# MCU.net
KiCad netlist of a schematic drawn in Altium Designer
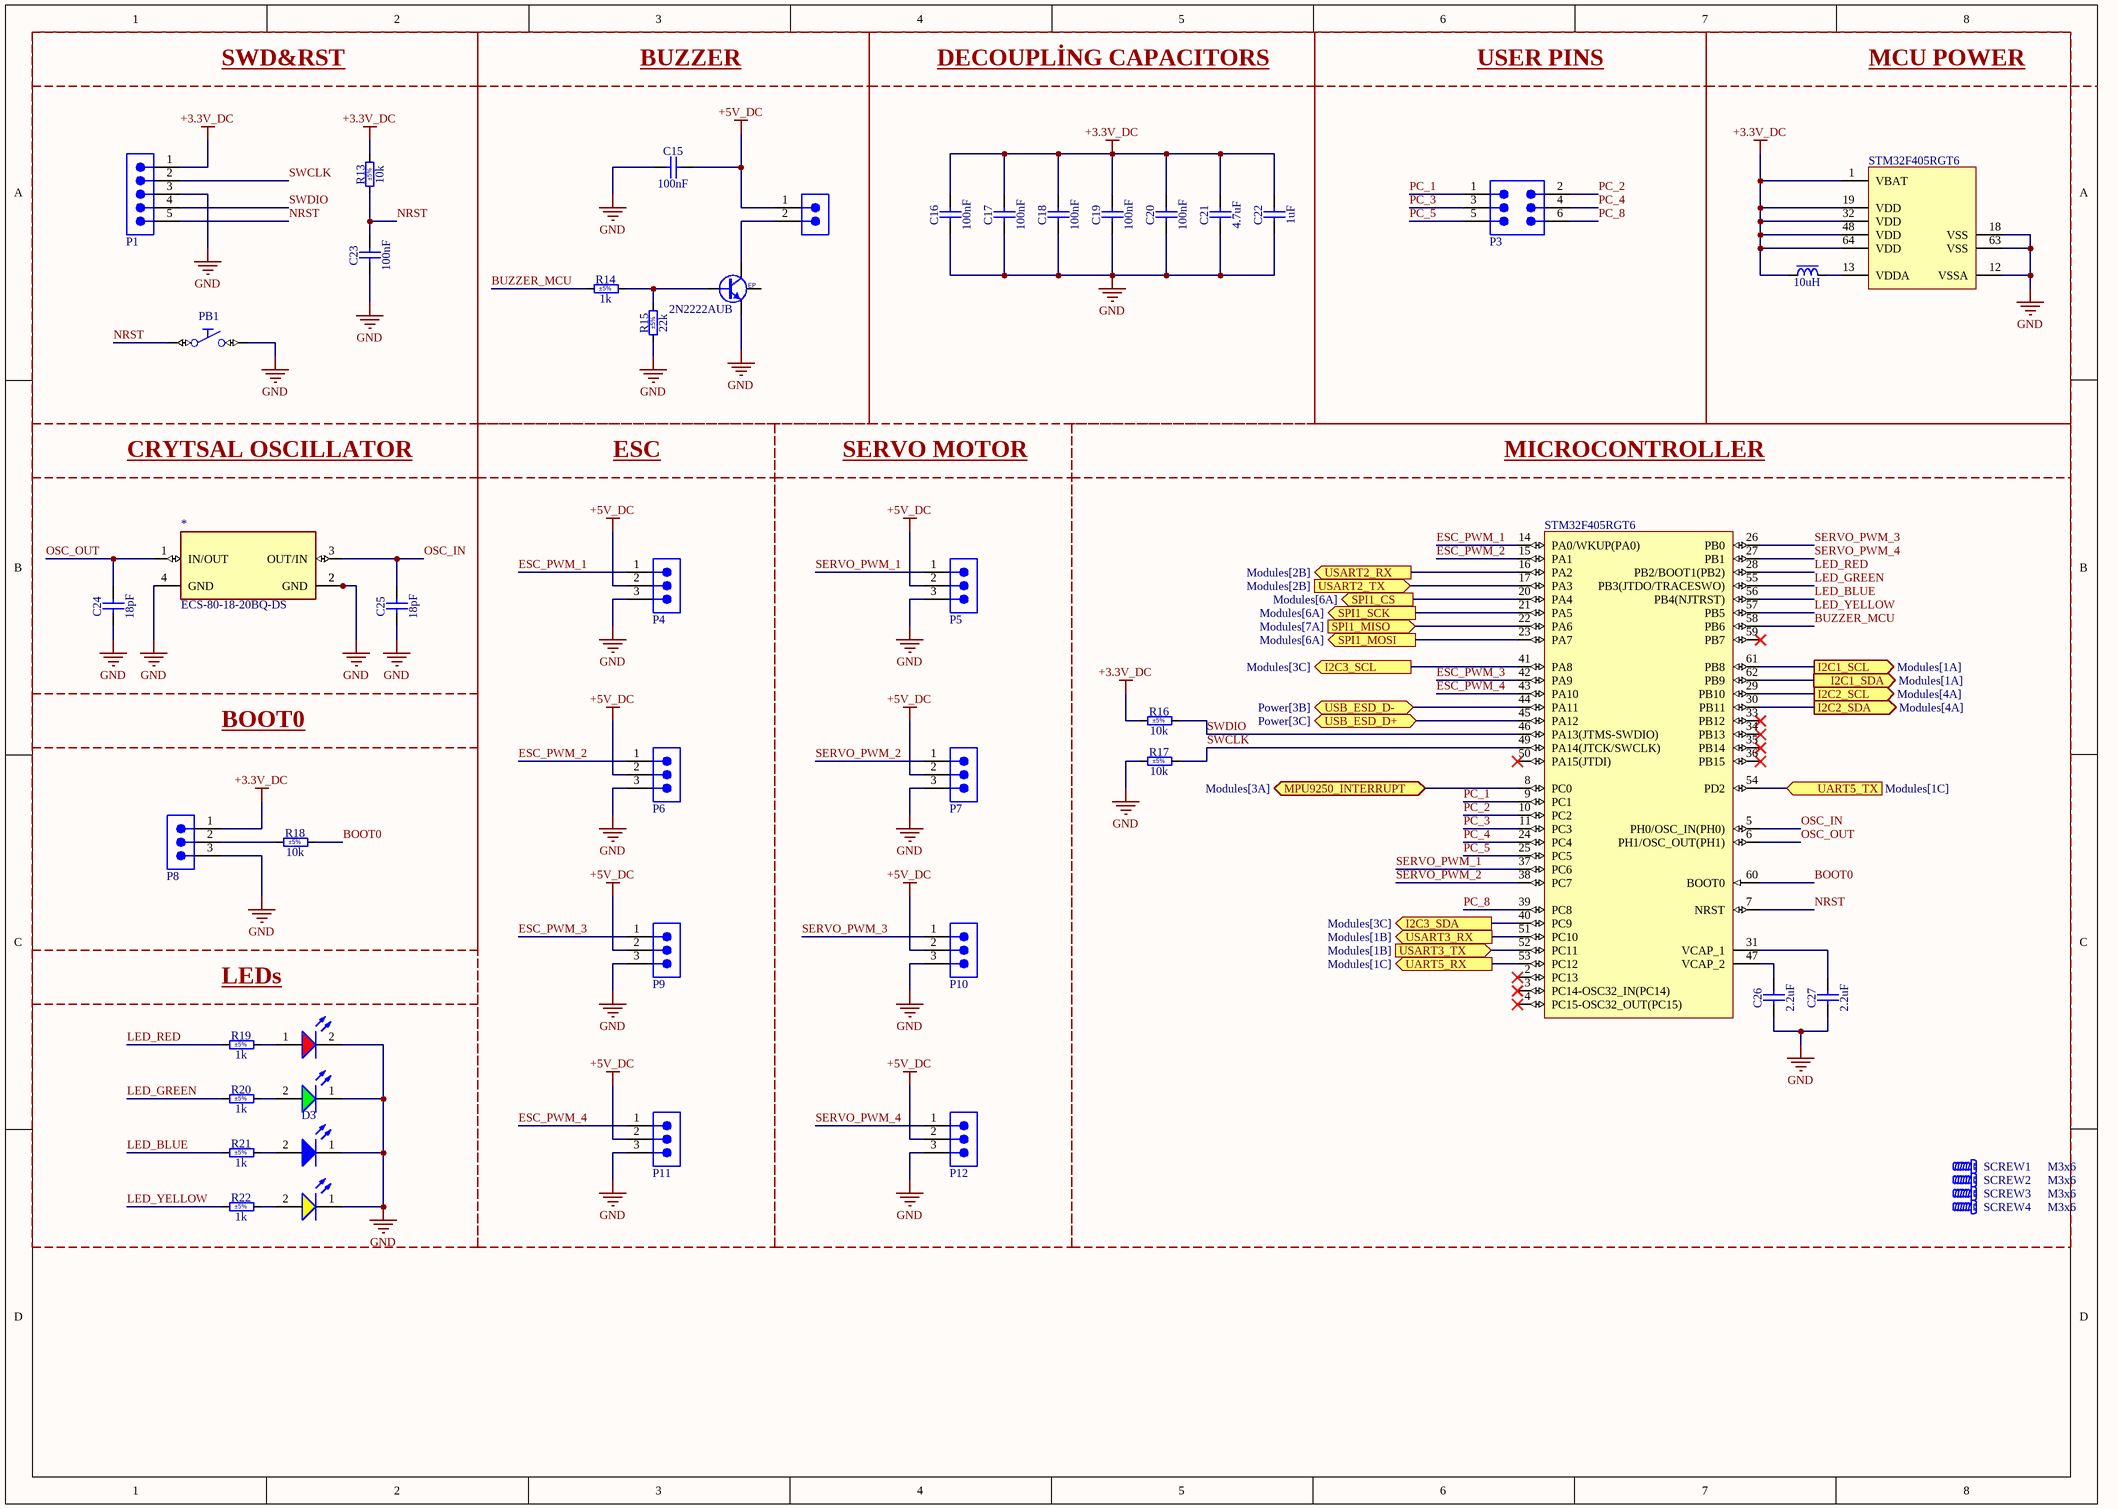
[diagram p0: MCU.SchDoc]

(export (version "E")
  (design (tool "Eeschema 10.0.6"))
  (components
    (comp (ref "*")
      (value "ECS-80-18-20BQ-DS")
      (footprint "ECS-80-18-20BQ-DS")
      (libsource (lib "UDEMY_Library") (part "ECS-80-18-20BQ-DS"))
    )
    (comp (ref "C15")
      (value "100nF")
      (footprint "CAPC2012X135N")
      (description "Non-polarised capacitor")
      (fields
        (field (name "PART NUMBER") "CC0805_100NF_50V_10%_X7R")
        (field (name "VOLTAGE") "50V")
        (field (name "AUTHOR") "CERN DEM JLC")
      )
      (libsource (lib "Capacitors") (part "Capacitor - non polarized"))
    )
    (comp (ref "C16")
      (value "100nF")
      (footprint "CAPC2012X135N")
      (description "Non-polarised capacitor")
      (fields
        (field (name "PART NUMBER") "CC0805_100NF_50V_10%_X7R")
        (field (name "VOLTAGE") "50V")
        (field (name "AUTHOR") "CERN DEM JLC")
      )
      (libsource (lib "Capacitors") (part "Capacitor - non polarized"))
    )
    (comp (ref "C17")
      (value "100nF")
      (footprint "CAPC2012X135N")
      (description "Non-polarised capacitor")
      (fields
        (field (name "PART NUMBER") "CC0805_100NF_50V_10%_X7R")
        (field (name "VOLTAGE") "50V")
        (field (name "AUTHOR") "CERN DEM JLC")
      )
      (libsource (lib "Capacitors") (part "Capacitor - non polarized"))
    )
    (comp (ref "C18")
      (value "100nF")
      (footprint "CAPC2012X135N")
      (description "Non-polarised capacitor")
      (fields
        (field (name "PART NUMBER") "CC0805_100NF_50V_10%_X7R")
        (field (name "VOLTAGE") "50V")
        (field (name "AUTHOR") "CERN DEM JLC")
      )
      (libsource (lib "Capacitors") (part "Capacitor - non polarized"))
    )
    (comp (ref "C19")
      (value "100nF")
      (footprint "CAPC2012X135N")
      (description "Non-polarised capacitor")
      (fields
        (field (name "PART NUMBER") "CC0805_100NF_50V_10%_X7R")
        (field (name "VOLTAGE") "50V")
        (field (name "AUTHOR") "CERN DEM JLC")
      )
      (libsource (lib "Capacitors") (part "Capacitor - non polarized"))
    )
    (comp (ref "C20")
      (value "100nF")
      (footprint "CAPC2012X135N")
      (description "Non-polarised capacitor")
      (fields
        (field (name "PART NUMBER") "CC0805_100NF_50V_10%_X7R")
        (field (name "VOLTAGE") "50V")
        (field (name "AUTHOR") "CERN DEM JLC")
      )
      (libsource (lib "Capacitors") (part "Capacitor - non polarized"))
    )
    (comp (ref "C21")
      (value "4.7uF")
      (footprint "CAPC2012X135N")
      (description "Non-polarised capacitor")
      (fields
        (field (name "PART NUMBER") "CC0805_4.7UF_10V_10%_X5R")
        (field (name "VOLTAGE") "10V")
        (field (name "AUTHOR") "CERN DEM JLC")
      )
      (libsource (lib "Capacitors") (part "Capacitor - non polarized"))
    )
    (comp (ref "C22")
      (value "1uF")
      (footprint "CAPC2012X145N")
      (description "Non-polarised capacitor")
      (fields
        (field (name "PART NUMBER") "CC0805_1UF_100V_10%_X7S_YUDEN_HMK212BC7105KGHTE")
        (field (name "VOLTAGE") "100V")
        (field (name "AUTHOR") "CERN DEM JLC")
      )
      (libsource (lib "Capacitors") (part "Capacitor - non polarized"))
    )
    (comp (ref "C23")
      (value "100nF")
      (footprint "CAPC2012X135N")
      (description "Non-polarised capacitor")
      (fields
        (field (name "PART NUMBER") "CC0805_100NF_50V_10%_X7R")
        (field (name "VOLTAGE") "50V")
        (field (name "AUTHOR") "CERN DEM JLC")
      )
      (libsource (lib "Capacitors") (part "Capacitor - non polarized"))
    )
    (comp (ref "C24")
      (value "18pF")
      (footprint "CAPC2012X135N")
      (description "Non-polarised capacitor")
      (fields
        (field (name "PART NUMBER") "CC0805_18PF_50V_5%_NP0")
        (field (name "VOLTAGE") "50V")
        (field (name "AUTHOR") "CERN DEM JLC")
      )
      (libsource (lib "Capacitors") (part "Capacitor - non polarized"))
    )
    (comp (ref "C25")
      (value "18pF")
      (footprint "CAPC2012X135N")
      (description "Non-polarised capacitor")
      (fields
        (field (name "PART NUMBER") "CC0805_18PF_50V_5%_NP0")
        (field (name "VOLTAGE") "50V")
        (field (name "AUTHOR") "CERN DEM JLC")
      )
      (libsource (lib "Capacitors") (part "Capacitor - non polarized"))
    )
    (comp (ref "C26")
      (value "2.2uF")
      (footprint "CAPC2012X135N")
      (description "Non-polarised capacitor")
      (fields
        (field (name "PART NUMBER") "CC0805_2.2UF_16V_10%_X7R")
        (field (name "VOLTAGE") "16V")
        (field (name "AUTHOR") "CERN DEM JLC")
      )
      (libsource (lib "Capacitors") (part "Capacitor - non polarized"))
    )
    (comp (ref "C27")
      (value "2.2uF")
      (footprint "CAPC2012X135N")
      (description "Non-polarised capacitor")
      (fields
        (field (name "PART NUMBER") "CC0805_2.2UF_16V_10%_X7R")
        (field (name "VOLTAGE") "16V")
        (field (name "AUTHOR") "CERN DEM JLC")
      )
      (libsource (lib "Capacitors") (part "Capacitor - non polarized"))
    )
    (comp (ref "D3")
      (value "Blue, 3.2V, 140°")
      (footprint "WL-SMCW_0603_150060xx75020")
      (description "WL-SMCW Mono-color Chip LED Waterclear, size 0603, Blue, 3.2V, 140°")
      (fields
        (field (name "MANUFACTURER PART NUMBER") "150060BS75020")
        (field (name "MANUFACTURER") "Wurth Elektronik")
      )
      (libsource (lib "WE - Optoelectronic Components") (part "LED_Blue_2A-1K"))
    )
    (comp (ref "D5")
      (value "Red, 2V, 140°")
      (footprint "WL-SMCW_0603_150060xx75003")
      (description "WL-SMCW Mono-color Chip LED Waterclear, size 0603, Red, 2V, 140°")
      (fields
        (field (name "MANUFACTURER PART NUMBER") "150060RS75003")
        (field (name "MANUFACTURER") "Wurth Elektronik")
      )
      (libsource (lib "WE - Optoelectronic Components") (part "LED_Red_1A-2K"))
    )
    (comp (ref "D6")
      (value "Bright Green, 2V, 140°")
      (footprint "WL-SMCD_0603")
      (description "WL-SMCD Mono-color Chip LED Diffused, SMT, size 0603, Bright Green, 2V, 140°")
      (fields
        (field (name "MANUFACTURER PART NUMBER") "150060VS55040")
        (field (name "MANUFACTURER") "Wurth Elektronik")
      )
      (libsource (lib "WE - Optoelectronic Components") (part "LED_Green_2A-1K"))
    )
    (comp (ref "D8")
      (value "Yellow, 2V, 140°")
      (footprint "WL-SMCD_0603")
      (description "WL-SMCD Mono-color Chip LED Diffused, SMT, size 0603, Yellow, 2V, 140°")
      (fields
        (field (name "MANUFACTURER PART NUMBER") "150060YS55040")
        (field (name "MANUFACTURER") "Wurth Elektronik")
      )
      (libsource (lib "WE - Optoelectronic Components") (part "LED_Yellow_2A-1K"))
    )
    (comp (ref "IC1")
      (value "STM32F405RGT6")
      (footprint "QFP50P1200X1200X160-64N")
      (fields (field (name "MANUFACTURER") "ST MICROELECTRONICS") (field (name "AUTHOR") "CERN DEM JLC"))
      (libsource (lib "ICs And Semiconductors") (part "STM32F405RGT6"))
    )
    (comp (ref "L3")
      (value "10uH")
      (footprint "IND_MURATA-PS_8200")
      (description "Inductor With Core")
      (fields
        (field (name "PART NUMBER") "IND_10UH_10%_MURATA-PS_8200")
        (field (name "POWER") "500mA")
        (field (name "AUTHOR") "CERN DEM JLC")
      )
      (libsource (lib "Inductors & Transformers") (part "Inductor With Magnetic core"))
    )
    (comp (ref "P1")
      (value "61300511121")
      (footprint "61300511121")
      (description "WR-PHD Pin Header, THT, Vertical, pitch 2.54mm, 1 Row, 5P")
      (fields (field (name "MANUFACTURER") "Wurth Elektronik"))
      (libsource (lib "WE - Electromechanical Components") (part "Header_Male_1R_05P"))
    )
    (comp (ref "P2")
      (value "691322310002")
      (footprint "691322310002")
      (description "WR-TBL Series 322 Horizontal PCB Header, THT, pitch 3.81mm, 2p")
      (fields (field (name "MANUFACTURER") "Wurth Elektronik"))
      (libsource (lib "WE - Electromechanical Components") (part "TBL - 1R - 02P - Male"))
    )
    (comp (ref "P3")
      (value "61300621121")
      (footprint "61300621121")
      (description "WR-PHD Pin Header, THT, Vertical, pitch 2.54mm, 2 Row, 6P")
      (fields (field (name "MANUFACTURER") "Wurth Elektronik"))
      (libsource (lib "WE - Electromechanical Components") (part "Header_Male_2R_06P"))
    )
    (comp (ref "P4")
      (value "61300311121")
      (footprint "61300311121")
      (description "WR-PHD Pin Header, THT, Vertical, pitch 2.54mm, 1 Row, 3P")
      (fields (field (name "MANUFACTURER") "Wurth Elektronik"))
      (libsource (lib "WE - Electromechanical Components") (part "Header_Male_1R_03P"))
    )
    (comp (ref "P5")
      (value "61300311121")
      (footprint "61300311121")
      (description "WR-PHD Pin Header, THT, Vertical, pitch 2.54mm, 1 Row, 3P")
      (fields (field (name "MANUFACTURER") "Wurth Elektronik"))
      (libsource (lib "WE - Electromechanical Components") (part "Header_Male_1R_03P"))
    )
    (comp (ref "P6")
      (value "61300311121")
      (footprint "61300311121")
      (description "WR-PHD Pin Header, THT, Vertical, pitch 2.54mm, 1 Row, 3P")
      (fields (field (name "MANUFACTURER") "Wurth Elektronik"))
      (libsource (lib "WE - Electromechanical Components") (part "Header_Male_1R_03P"))
    )
    (comp (ref "P7")
      (value "61300311121")
      (footprint "61300311121")
      (description "WR-PHD Pin Header, THT, Vertical, pitch 2.54mm, 1 Row, 3P")
      (fields (field (name "MANUFACTURER") "Wurth Elektronik"))
      (libsource (lib "WE - Electromechanical Components") (part "Header_Male_1R_03P"))
    )
    (comp (ref "P8")
      (value "61300311121")
      (footprint "61300311121")
      (description "WR-PHD Pin Header, THT, Vertical, pitch 2.54mm, 1 Row, 3P")
      (fields (field (name "MANUFACTURER") "Wurth Elektronik"))
      (libsource (lib "WE - Electromechanical Components") (part "Header_Male_1R_03P"))
    )
    (comp (ref "P9")
      (value "61300311121")
      (footprint "61300311121")
      (description "WR-PHD Pin Header, THT, Vertical, pitch 2.54mm, 1 Row, 3P")
      (fields (field (name "MANUFACTURER") "Wurth Elektronik"))
      (libsource (lib "WE - Electromechanical Components") (part "Header_Male_1R_03P"))
    )
    (comp (ref "P10")
      (value "61300311121")
      (footprint "61300311121")
      (description "WR-PHD Pin Header, THT, Vertical, pitch 2.54mm, 1 Row, 3P")
      (fields (field (name "MANUFACTURER") "Wurth Elektronik"))
      (libsource (lib "WE - Electromechanical Components") (part "Header_Male_1R_03P"))
    )
    (comp (ref "P11")
      (value "61300311121")
      (footprint "61300311121")
      (description "WR-PHD Pin Header, THT, Vertical, pitch 2.54mm, 1 Row, 3P")
      (fields (field (name "MANUFACTURER") "Wurth Elektronik"))
      (libsource (lib "WE - Electromechanical Components") (part "Header_Male_1R_03P"))
    )
    (comp (ref "P12")
      (value "61300311121")
      (footprint "61300311121")
      (description "WR-PHD Pin Header, THT, Vertical, pitch 2.54mm, 1 Row, 3P")
      (fields (field (name "MANUFACTURER") "Wurth Elektronik"))
      (libsource (lib "WE - Electromechanical Components") (part "Header_Male_1R_03P"))
    )
    (comp (ref "PB1")
      (value "Push Button")
      (footprint "PB_C&K_KSR2xxGLF")
      (description "Push-Button Switch SPST")
      (fields
        (field (name "PART NUMBER") "PB_C&K_KSR223GLFG")
        (field (name "MANUFACTURER") "C&K")
        (field (name "AUTHOR") "CERN DEM HF")
      )
      (libsource (lib "Eletro-mechanical") (part "PB SPST 1C-2NO"))
    )
    (comp (ref "R13")
      (value "10k")
      (footprint "RESC2012X60N")
      (description "Resistor - 0.1%")
      (fields
        (field (name "TOLERANCE") "±5%")
        (field (name "PART NUMBER") "R0805_10K_0.1%_0.1W_10PPM")
        (field (name "POWER") "0.1W")
        (field (name "AUTHOR") "CERN DEM JLC")
      )
      (libsource (lib "Resistors") (part "Resistor - 0.1%"))
    )
    (comp (ref "R14")
      (value "1k")
      (footprint "RESC2012X60N")
      (description "Resistor - 0.1%")
      (fields
        (field (name "TOLERANCE") "±5%")
        (field (name "PART NUMBER") "R0805_1K_0.1%_0.125W_25PPM")
        (field (name "POWER") "0.125W")
        (field (name "AUTHOR") "CERN DEM JLC")
      )
      (libsource (lib "Resistors") (part "Resistor - 0.1%"))
    )
    (comp (ref "R15")
      (value "22k")
      (footprint "RESC2012X60N")
      (description "Resistor - 1%")
      (fields
        (field (name "TOLERANCE") "±5%")
        (field (name "PART NUMBER") "R0805_22K_1%_0.125W_100PPM")
        (field (name "POWER") "0.125W")
        (field (name "AUTHOR") "CERN DEM JLC")
      )
      (libsource (lib "Resistors") (part "Resistor - 1%"))
    )
    (comp (ref "R16")
      (value "10k")
      (footprint "RESC2012X60N")
      (description "Resistor - 0.1%")
      (fields
        (field (name "TOLERANCE") "±5%")
        (field (name "PART NUMBER") "R0805_10K_0.1%_0.1W_10PPM")
        (field (name "POWER") "0.1W")
        (field (name "AUTHOR") "CERN DEM JLC")
      )
      (libsource (lib "Resistors") (part "Resistor - 0.1%"))
    )
    (comp (ref "R17")
      (value "10k")
      (footprint "RESC2012X60N")
      (description "Resistor - 0.1%")
      (fields
        (field (name "TOLERANCE") "±5%")
        (field (name "PART NUMBER") "R0805_10K_0.1%_0.1W_10PPM")
        (field (name "POWER") "0.1W")
        (field (name "AUTHOR") "CERN DEM JLC")
      )
      (libsource (lib "Resistors") (part "Resistor - 0.1%"))
    )
    (comp (ref "R18")
      (value "10k")
      (footprint "RESC2012X60N")
      (description "Resistor - 1%")
      (fields
        (field (name "TOLERANCE") "±5%")
        (field (name "PART NUMBER") "R0805_100K_1%_0.125W_100PPM")
        (field (name "POWER") "0.125W")
        (field (name "AUTHOR") "CERN DEM JLC")
      )
      (libsource (lib "Resistors") (part "Resistor - 1%"))
    )
    (comp (ref "R19")
      (value "1k")
      (footprint "RESC2012X60N")
      (description "Resistor - 0.1%")
      (fields
        (field (name "TOLERANCE") "±5%")
        (field (name "PART NUMBER") "R0805_1K_0.1%_0.125W_25PPM")
        (field (name "POWER") "0.125W")
        (field (name "AUTHOR") "CERN DEM JLC")
      )
      (libsource (lib "Resistors") (part "Resistor - 0.1%"))
    )
    (comp (ref "R20")
      (value "1k")
      (footprint "RESC2012X60N")
      (description "Resistor - 0.1%")
      (fields
        (field (name "TOLERANCE") "±5%")
        (field (name "PART NUMBER") "R0805_1K_0.1%_0.125W_25PPM")
        (field (name "POWER") "0.125W")
        (field (name "AUTHOR") "CERN DEM JLC")
      )
      (libsource (lib "Resistors") (part "Resistor - 0.1%"))
    )
    (comp (ref "R21")
      (value "1k")
      (footprint "RESC2012X60N")
      (description "Resistor - 0.1%")
      (fields
        (field (name "TOLERANCE") "±5%")
        (field (name "PART NUMBER") "R0805_1K_0.1%_0.125W_25PPM")
        (field (name "POWER") "0.125W")
        (field (name "AUTHOR") "CERN DEM JLC")
      )
      (libsource (lib "Resistors") (part "Resistor - 0.1%"))
    )
    (comp (ref "R22")
      (value "1k")
      (footprint "RESC2012X60N")
      (description "Resistor - 0.1%")
      (fields
        (field (name "TOLERANCE") "±5%")
        (field (name "PART NUMBER") "R0805_1K_0.1%_0.125W_25PPM")
        (field (name "POWER") "0.125W")
        (field (name "AUTHOR") "CERN DEM JLC")
      )
      (libsource (lib "Resistors") (part "Resistor - 0.1%"))
    )
    (comp (ref "SCREW1")
      (value "M3x6")
      (footprint "BOSSARD_BN5687-3061605_v")
      (description "Screw")
      (fields
        (field (name "PART NUMBER") "BOSSARD_BN5687-3061605_v")
        (field (name "MANUFACTURER") "BOSSARD")
        (field (name "AUTHOR") "CERN DEM JLC")
      )
      (libsource (lib "Eletro-mechanical") (part "Screw"))
    )
    (comp (ref "SCREW2")
      (value "M3x6")
      (footprint "BOSSARD_BN5687-3061605_v")
      (description "Screw")
      (fields
        (field (name "PART NUMBER") "BOSSARD_BN5687-3061605_v")
        (field (name "MANUFACTURER") "BOSSARD")
        (field (name "AUTHOR") "CERN DEM JLC")
      )
      (libsource (lib "Eletro-mechanical") (part "Screw"))
    )
    (comp (ref "SCREW3")
      (value "M3x6")
      (footprint "BOSSARD_BN5687-3061605_v")
      (description "Screw")
      (fields
        (field (name "PART NUMBER") "BOSSARD_BN5687-3061605_v")
        (field (name "MANUFACTURER") "BOSSARD")
        (field (name "AUTHOR") "CERN DEM JLC")
      )
      (libsource (lib "Eletro-mechanical") (part "Screw"))
    )
    (comp (ref "SCREW4")
      (value "M3x6")
      (footprint "BOSSARD_BN5687-3061605_v")
      (description "Screw")
      (fields
        (field (name "PART NUMBER") "BOSSARD_BN5687-3061605_v")
        (field (name "MANUFACTURER") "BOSSARD")
        (field (name "AUTHOR") "CERN DEM JLC")
      )
      (libsource (lib "Eletro-mechanical") (part "Screw"))
    )
    (comp (ref "T1")
      (value "2N2222AUB")
      (footprint "MICROSEMI_UB")
      (description "NPN Transistor + Exposed Pad")
      (fields (field (name "MANUFACTURER") "MICROSEMI") (field (name "AUTHOR") "CERN DEM BC"))
      (libsource (lib "ICs And Semiconductors") (part "NPN B1 E2 C3 EP4"))
    )
  )
  (nets
    (net (code "1") (name "+3.3V_DC") (class "Default")
      (node (ref "C16") (pin "2") (pinfunction "2_2") (pintype "passive"))
      (node (ref "C17") (pin "2") (pinfunction "2_2") (pintype "passive"))
      (node (ref "C18") (pin "2") (pinfunction "2_2") (pintype "passive"))
      (node (ref "C19") (pin "2") (pinfunction "2_2") (pintype "passive"))
      (node (ref "C20") (pin "2") (pinfunction "2_2") (pintype "passive"))
      (node (ref "C21") (pin "2") (pinfunction "2_2") (pintype "passive"))
      (node (ref "C22") (pin "2") (pinfunction "2_2") (pintype "passive"))
      (node (ref "IC1") (pin "1") (pinfunction "VBAT_1") (pintype "power_in"))
      (node (ref "IC1") (pin "19") (pinfunction "VDD_19") (pintype "power_in"))
      (node (ref "IC1") (pin "32") (pinfunction "VDD_32") (pintype "power_in"))
      (node (ref "IC1") (pin "48") (pinfunction "VDD_48") (pintype "power_in"))
      (node (ref "IC1") (pin "64") (pinfunction "VDD_64") (pintype "power_in"))
      (node (ref "L3") (pin "1") (pinfunction "1_1") (pintype "passive"))
      (node (ref "P1") (pin "1") (pinfunction "1_1") (pintype "passive"))
      (node (ref "P8") (pin "1") (pinfunction "1_1") (pintype "passive"))
      (node (ref "R13") (pin "2") (pinfunction "2_2") (pintype "passive"))
      (node (ref "R16") (pin "1") (pinfunction "1_1") (pintype "passive"))
    )
    (net (code "2") (name "+5V_DC") (class "Default")
      (node (ref "C15") (pin "2") (pinfunction "2_2") (pintype "passive"))
      (node (ref "P10") (pin "2") (pinfunction "2_2") (pintype "passive"))
      (node (ref "P11") (pin "2") (pinfunction "2_2") (pintype "passive"))
      (node (ref "P12") (pin "2") (pinfunction "2_2") (pintype "passive"))
      (node (ref "P2") (pin "1") (pinfunction "1_1") (pintype "passive"))
      (node (ref "P4") (pin "2") (pinfunction "2_2") (pintype "passive"))
      (node (ref "P5") (pin "2") (pinfunction "2_2") (pintype "passive"))
      (node (ref "P6") (pin "2") (pinfunction "2_2") (pintype "passive"))
      (node (ref "P7") (pin "2") (pinfunction "2_2") (pintype "passive"))
      (node (ref "P9") (pin "2") (pinfunction "2_2") (pintype "passive"))
    )
    (net (code "3") (name "/BOOT0") (class "Default")
      (node (ref "IC1") (pin "60") (pinfunction "BOOT0_60") (pintype "input"))
      (node (ref "R18") (pin "2") (pinfunction "2_2") (pintype "passive"))
    )
    (net (code "4") (name "/BUZZER_MCU") (class "Default")
      (node (ref "IC1") (pin "58") (pinfunction "PB6_58") (pintype "bidirectional"))
      (node (ref "R14") (pin "1") (pinfunction "1_1") (pintype "passive"))
    )
    (net (code "5") (name "/ESC_PWM_1") (class "Default")
      (node (ref "IC1") (pin "14") (pinfunction "PA0/WKUP(PA0)_14") (pintype "bidirectional"))
      (node (ref "P4") (pin "1") (pinfunction "1_1") (pintype "passive"))
    )
    (net (code "6") (name "/ESC_PWM_2") (class "Default")
      (node (ref "IC1") (pin "15") (pinfunction "PA1_15") (pintype "bidirectional"))
      (node (ref "P6") (pin "1") (pinfunction "1_1") (pintype "passive"))
    )
    (net (code "7") (name "/ESC_PWM_3") (class "Default")
      (node (ref "IC1") (pin "42") (pinfunction "PA9_42") (pintype "bidirectional"))
      (node (ref "P9") (pin "1") (pinfunction "1_1") (pintype "passive"))
    )
    (net (code "8") (name "/ESC_PWM_4") (class "Default")
      (node (ref "IC1") (pin "43") (pinfunction "PA10_43") (pintype "bidirectional"))
      (node (ref "P11") (pin "1") (pinfunction "1_1") (pintype "passive"))
    )
    (net (code "9") (name "/I2C1_SCL") (class "Default")
      (node (ref "IC1") (pin "61") (pinfunction "PB8_61") (pintype "bidirectional"))
    )
    (net (code "10") (name "/I2C1_SDA") (class "Default")
      (node (ref "IC1") (pin "62") (pinfunction "PB9_62") (pintype "bidirectional"))
    )
    (net (code "11") (name "/I2C2_SCL") (class "Default")
      (node (ref "IC1") (pin "29") (pinfunction "PB10_29") (pintype "bidirectional"))
    )
    (net (code "12") (name "/I2C2_SDA") (class "Default")
      (node (ref "IC1") (pin "30") (pinfunction "PB11_30") (pintype "bidirectional"))
    )
    (net (code "13") (name "/I2C3_SCL") (class "Default")
      (node (ref "IC1") (pin "41") (pinfunction "PA8_41") (pintype "bidirectional"))
    )
    (net (code "14") (name "/I2C3_SDA") (class "Default")
      (node (ref "IC1") (pin "40") (pinfunction "PC9_40") (pintype "bidirectional"))
    )
    (net (code "15") (name "/LED_BLUE") (class "Default")
      (node (ref "IC1") (pin "56") (pinfunction "PB4(NJTRST)_56") (pintype "bidirectional"))
      (node (ref "R21") (pin "1") (pinfunction "1_1") (pintype "passive"))
    )
    (net (code "16") (name "/LED_GREEN") (class "Default")
      (node (ref "IC1") (pin "55") (pinfunction "PB3(JTDO/TRACESWO)_55") (pintype "bidirectional"))
      (node (ref "R20") (pin "1") (pinfunction "1_1") (pintype "passive"))
    )
    (net (code "17") (name "/LED_RED") (class "Default")
      (node (ref "IC1") (pin "28") (pinfunction "PB2/BOOT1(PB2)_28") (pintype "bidirectional"))
      (node (ref "R19") (pin "1") (pinfunction "1_1") (pintype "passive"))
    )
    (net (code "18") (name "/LED_YELLOW") (class "Default")
      (node (ref "IC1") (pin "57") (pinfunction "PB5_57") (pintype "bidirectional"))
      (node (ref "R22") (pin "1") (pinfunction "1_1") (pintype "passive"))
    )
    (net (code "19") (name "/MPU9250_INTERRUPT") (class "Default")
      (node (ref "IC1") (pin "8") (pinfunction "PC0_8") (pintype "bidirectional"))
    )
    (net (code "20") (name "/NRST") (class "Default")
      (node (ref "C23") (pin "2") (pinfunction "2_2") (pintype "passive"))
      (node (ref "IC1") (pin "7") (pinfunction "NRST_7") (pintype "bidirectional"))
      (node (ref "P1") (pin "5") (pinfunction "5_5") (pintype "passive"))
      (node (ref "PB1") (pin "1") (pinfunction "C_1") (pintype "bidirectional"))
      (node (ref "R13") (pin "1") (pinfunction "1_1") (pintype "passive"))
    )
    (net (code "21") (name "/OSC_IN") (class "Default")
      (node (ref "*") (pin "3") (pinfunction "OUT/IN_3") (pintype "bidirectional"))
      (node (ref "C25") (pin "2") (pinfunction "2_2") (pintype "passive"))
      (node (ref "IC1") (pin "5") (pinfunction "PH0/OSC_IN(PH0)_5") (pintype "bidirectional"))
    )
    (net (code "22") (name "/OSC_OUT") (class "Default")
      (node (ref "*") (pin "1") (pinfunction "IN/OUT_1") (pintype "bidirectional"))
      (node (ref "C24") (pin "2") (pinfunction "2_2") (pintype "passive"))
      (node (ref "IC1") (pin "6") (pinfunction "PH1/OSC_OUT(PH1)_6") (pintype "bidirectional"))
    )
    (net (code "23") (name "/PC_1") (class "Default")
      (node (ref "IC1") (pin "9") (pinfunction "PC1_9") (pintype "bidirectional"))
      (node (ref "P3") (pin "1") (pinfunction "1_1") (pintype "passive"))
    )
    (net (code "24") (name "/PC_2") (class "Default")
      (node (ref "IC1") (pin "10") (pinfunction "PC2_10") (pintype "bidirectional"))
      (node (ref "P3") (pin "2") (pinfunction "2_2") (pintype "passive"))
    )
    (net (code "25") (name "/PC_3") (class "Default")
      (node (ref "IC1") (pin "11") (pinfunction "PC3_11") (pintype "bidirectional"))
      (node (ref "P3") (pin "3") (pinfunction "3_3") (pintype "passive"))
    )
    (net (code "26") (name "/PC_4") (class "Default")
      (node (ref "IC1") (pin "24") (pinfunction "PC4_24") (pintype "bidirectional"))
      (node (ref "P3") (pin "4") (pinfunction "4_4") (pintype "passive"))
    )
    (net (code "27") (name "/PC_5") (class "Default")
      (node (ref "IC1") (pin "25") (pinfunction "PC5_25") (pintype "bidirectional"))
      (node (ref "P3") (pin "5") (pinfunction "5_5") (pintype "passive"))
    )
    (net (code "28") (name "/PC_8") (class "Default")
      (node (ref "IC1") (pin "39") (pinfunction "PC8_39") (pintype "bidirectional"))
      (node (ref "P3") (pin "6") (pinfunction "6_6") (pintype "passive"))
    )
    (net (code "29") (name "/SERVO_PWM_1") (class "Default")
      (node (ref "IC1") (pin "37") (pinfunction "PC6_37") (pintype "bidirectional"))
      (node (ref "P5") (pin "1") (pinfunction "1_1") (pintype "passive"))
    )
    (net (code "30") (name "/SERVO_PWM_2") (class "Default")
      (node (ref "IC1") (pin "38") (pinfunction "PC7_38") (pintype "bidirectional"))
      (node (ref "P7") (pin "1") (pinfunction "1_1") (pintype "passive"))
    )
    (net (code "31") (name "/SERVO_PWM_3") (class "Default")
      (node (ref "IC1") (pin "26") (pinfunction "PB0_26") (pintype "bidirectional"))
      (node (ref "P10") (pin "1") (pinfunction "1_1") (pintype "passive"))
    )
    (net (code "32") (name "/SERVO_PWM_4") (class "Default")
      (node (ref "IC1") (pin "27") (pinfunction "PB1_27") (pintype "bidirectional"))
      (node (ref "P12") (pin "1") (pinfunction "1_1") (pintype "passive"))
    )
    (net (code "33") (name "/SPI1_CS") (class "Default")
      (node (ref "IC1") (pin "20") (pinfunction "PA4_20") (pintype "bidirectional"))
    )
    (net (code "34") (name "/SPI1_MISO") (class "Default")
      (node (ref "IC1") (pin "22") (pinfunction "PA6_22") (pintype "bidirectional"))
    )
    (net (code "35") (name "/SPI1_MOSI") (class "Default")
      (node (ref "IC1") (pin "23") (pinfunction "PA7_23") (pintype "bidirectional"))
    )
    (net (code "36") (name "/SPI1_SCK") (class "Default")
      (node (ref "IC1") (pin "21") (pinfunction "PA5_21") (pintype "bidirectional"))
    )
    (net (code "37") (name "/SWCLK") (class "Default")
      (node (ref "IC1") (pin "49") (pinfunction "PA14(JTCK/SWCLK)_49") (pintype "bidirectional"))
      (node (ref "P1") (pin "2") (pinfunction "2_2") (pintype "passive"))
      (node (ref "R17") (pin "2") (pinfunction "2_2") (pintype "passive"))
    )
    (net (code "38") (name "/SWDIO") (class "Default")
      (node (ref "IC1") (pin "46") (pinfunction "PA13(JTMS-SWDIO)_46") (pintype "bidirectional"))
      (node (ref "P1") (pin "4") (pinfunction "4_4") (pintype "passive"))
      (node (ref "R16") (pin "2") (pinfunction "2_2") (pintype "passive"))
    )
    (net (code "39") (name "/UART5_RX") (class "Default")
      (node (ref "IC1") (pin "53") (pinfunction "PC12_53") (pintype "bidirectional"))
    )
    (net (code "40") (name "/UART5_TX") (class "Default")
      (node (ref "IC1") (pin "54") (pinfunction "PD2_54") (pintype "bidirectional"))
    )
    (net (code "41") (name "/USART2_RX") (class "Default")
      (node (ref "IC1") (pin "16") (pinfunction "PA2_16") (pintype "bidirectional"))
    )
    (net (code "42") (name "/USART2_TX") (class "Default")
      (node (ref "IC1") (pin "17") (pinfunction "PA3_17") (pintype "bidirectional"))
    )
    (net (code "43") (name "/USART3_RX") (class "Default")
      (node (ref "IC1") (pin "51") (pinfunction "PC10_51") (pintype "bidirectional"))
    )
    (net (code "44") (name "/USART3_TX") (class "Default")
      (node (ref "IC1") (pin "52") (pinfunction "PC11_52") (pintype "bidirectional"))
    )
    (net (code "45") (name "/USB_ESD_D+") (class "Default")
      (node (ref "IC1") (pin "45") (pinfunction "PA12_45") (pintype "bidirectional"))
    )
    (net (code "46") (name "/USB_ESD_D-") (class "Default")
      (node (ref "IC1") (pin "44") (pinfunction "PA11_44") (pintype "bidirectional"))
    )
    (net (code "47") (name "GND") (class "Default")
      (node (ref "*") (pin "2") (pinfunction "GND_2") (pintype "power_in"))
      (node (ref "*") (pin "4") (pinfunction "GND_4") (pintype "power_in"))
      (node (ref "C15") (pin "1") (pinfunction "1_1") (pintype "passive"))
      (node (ref "C16") (pin "1") (pinfunction "1_1") (pintype "passive"))
      (node (ref "C17") (pin "1") (pinfunction "1_1") (pintype "passive"))
      (node (ref "C18") (pin "1") (pinfunction "1_1") (pintype "passive"))
      (node (ref "C19") (pin "1") (pinfunction "1_1") (pintype "passive"))
      (node (ref "C20") (pin "1") (pinfunction "1_1") (pintype "passive"))
      (node (ref "C21") (pin "1") (pinfunction "1_1") (pintype "passive"))
      (node (ref "C22") (pin "1") (pinfunction "1_1") (pintype "passive"))
      (node (ref "C23") (pin "1") (pinfunction "1_1") (pintype "passive"))
      (node (ref "C24") (pin "1") (pinfunction "1_1") (pintype "passive"))
      (node (ref "C25") (pin "1") (pinfunction "1_1") (pintype "passive"))
      (node (ref "C26") (pin "1") (pinfunction "1_1") (pintype "passive"))
      (node (ref "C27") (pin "1") (pinfunction "1_1") (pintype "passive"))
      (node (ref "D3") (pin "1") (pinfunction "K_1") (pintype "passive"))
      (node (ref "D5") (pin "2") (pinfunction "K_2") (pintype "passive"))
      (node (ref "D6") (pin "1") (pinfunction "K_1") (pintype "passive"))
      (node (ref "D8") (pin "1") (pinfunction "K_1") (pintype "passive"))
      (node (ref "IC1") (pin "12") (pinfunction "VSSA_12") (pintype "power_in"))
      (node (ref "IC1") (pin "18") (pinfunction "VSS_18") (pintype "power_in"))
      (node (ref "IC1") (pin "63") (pinfunction "VSS_63") (pintype "power_in"))
      (node (ref "P1") (pin "3") (pinfunction "3_3") (pintype "passive"))
      (node (ref "P10") (pin "3") (pinfunction "3_3") (pintype "passive"))
      (node (ref "P11") (pin "3") (pinfunction "3_3") (pintype "passive"))
      (node (ref "P12") (pin "3") (pinfunction "3_3") (pintype "passive"))
      (node (ref "P4") (pin "3") (pinfunction "3_3") (pintype "passive"))
      (node (ref "P5") (pin "3") (pinfunction "3_3") (pintype "passive"))
      (node (ref "P6") (pin "3") (pinfunction "3_3") (pintype "passive"))
      (node (ref "P7") (pin "3") (pinfunction "3_3") (pintype "passive"))
      (node (ref "P8") (pin "3") (pinfunction "3_3") (pintype "passive"))
      (node (ref "P9") (pin "3") (pinfunction "3_3") (pintype "passive"))
      (node (ref "PB1") (pin "2") (pinfunction "NO_2") (pintype "bidirectional"))
      (node (ref "R15") (pin "1") (pinfunction "1_1") (pintype "passive"))
      (node (ref "R17") (pin "1") (pinfunction "1_1") (pintype "passive"))
      (node (ref "T1") (pin "2") (pinfunction "E_2") (pintype "passive"))
    )
    (net (code "48") (name "Net-(D3-A)") (class "Default")
      (node (ref "D3") (pin "2") (pinfunction "A_2") (pintype "passive"))
      (node (ref "R21") (pin "2") (pinfunction "2_2") (pintype "passive"))
    )
    (net (code "49") (name "Net-(D5-A)") (class "Default")
      (node (ref "D5") (pin "1") (pinfunction "A_1") (pintype "passive"))
      (node (ref "R19") (pin "2") (pinfunction "2_2") (pintype "passive"))
    )
    (net (code "50") (name "Net-(D6-A)") (class "Default")
      (node (ref "D6") (pin "2") (pinfunction "A_2") (pintype "passive"))
      (node (ref "R20") (pin "2") (pinfunction "2_2") (pintype "passive"))
    )
    (net (code "51") (name "Net-(D8-A)") (class "Default")
      (node (ref "D8") (pin "2") (pinfunction "A_2") (pintype "passive"))
      (node (ref "R22") (pin "2") (pinfunction "2_2") (pintype "passive"))
    )
    (net (code "52") (name "Net-(IC1A-VCAP_1)") (class "Default")
      (node (ref "C27") (pin "2") (pinfunction "2_2") (pintype "passive"))
      (node (ref "IC1") (pin "31") (pinfunction "VCAP_1_31") (pintype "power_in"))
    )
    (net (code "53") (name "Net-(IC1A-VCAP_2)") (class "Default")
      (node (ref "C26") (pin "2") (pinfunction "2_2") (pintype "passive"))
      (node (ref "IC1") (pin "47") (pinfunction "VCAP_2_47") (pintype "power_in"))
    )
    (net (code "54") (name "Net-(IC1B-VDDA)") (class "Default")
      (node (ref "IC1") (pin "13") (pinfunction "VDDA_13") (pintype "power_in"))
      (node (ref "L3") (pin "2") (pinfunction "2_2") (pintype "passive"))
    )
    (net (code "55") (name "Net-(P8-Pad2)") (class "Default")
      (node (ref "P8") (pin "2") (pinfunction "2_2") (pintype "passive"))
      (node (ref "R18") (pin "1") (pinfunction "1_1") (pintype "passive"))
    )
    (net (code "56") (name "Net-(T1-B)") (class "Default")
      (node (ref "R14") (pin "2") (pinfunction "2_2") (pintype "passive"))
      (node (ref "R15") (pin "2") (pinfunction "2_2") (pintype "passive"))
      (node (ref "T1") (pin "1") (pinfunction "B_1") (pintype "passive"))
    )
    (net (code "57") (name "Net-(T1-C)") (class "Default")
      (node (ref "P2") (pin "2") (pinfunction "2_2") (pintype "passive"))
      (node (ref "T1") (pin "3") (pinfunction "C_3") (pintype "passive"))
    )
    (net (code "58") (name "unconnected-(IC1A-PA15(JTDI)-Pad50)") (class "Default")
      (node (ref "IC1") (pin "50") (pinfunction "PA15(JTDI)_50") (pintype "bidirectional+no_connect"))
    )
    (net (code "59") (name "unconnected-(IC1A-PB7-Pad59)") (class "Default")
      (node (ref "IC1") (pin "59") (pinfunction "PB7_59") (pintype "bidirectional+no_connect"))
    )
    (net (code "60") (name "unconnected-(IC1A-PB12-Pad33)") (class "Default")
      (node (ref "IC1") (pin "33") (pinfunction "PB12_33") (pintype "bidirectional+no_connect"))
    )
    (net (code "61") (name "unconnected-(IC1A-PB13-Pad34)") (class "Default")
      (node (ref "IC1") (pin "34") (pinfunction "PB13_34") (pintype "bidirectional+no_connect"))
    )
    (net (code "62") (name "unconnected-(IC1A-PB14-Pad35)") (class "Default")
      (node (ref "IC1") (pin "35") (pinfunction "PB14_35") (pintype "bidirectional+no_connect"))
    )
    (net (code "63") (name "unconnected-(IC1A-PB15-Pad36)") (class "Default")
      (node (ref "IC1") (pin "36") (pinfunction "PB15_36") (pintype "bidirectional+no_connect"))
    )
    (net (code "64") (name "unconnected-(IC1A-PC13-Pad2)") (class "Default")
      (node (ref "IC1") (pin "2") (pinfunction "PC13_2") (pintype "bidirectional+no_connect"))
    )
    (net (code "65") (name "unconnected-(IC1A-PC14-OSC32_IN(PC14)-Pad3)") (class "Default")
      (node (ref "IC1") (pin "3") (pinfunction "PC14-OSC32_IN(PC14)_3") (pintype "bidirectional+no_connect"))
    )
    (net (code "66") (name "unconnected-(IC1A-PC15-OSC32_OUT(PC15)-Pad4)") (class "Default")
      (node (ref "IC1") (pin "4") (pinfunction "PC15-OSC32_OUT(PC15)_4") (pintype "bidirectional+no_connect"))
    )
    (net (code "67") (name "unconnected-(T1-EP-Pad4)") (class "Default")
      (node (ref "T1") (pin "4") (pinfunction "EP_4") (pintype "passive"))
    )
  )
)
